# eeZeeSwitch.net
KiCad netlist of a schematic drawn in EAGLE
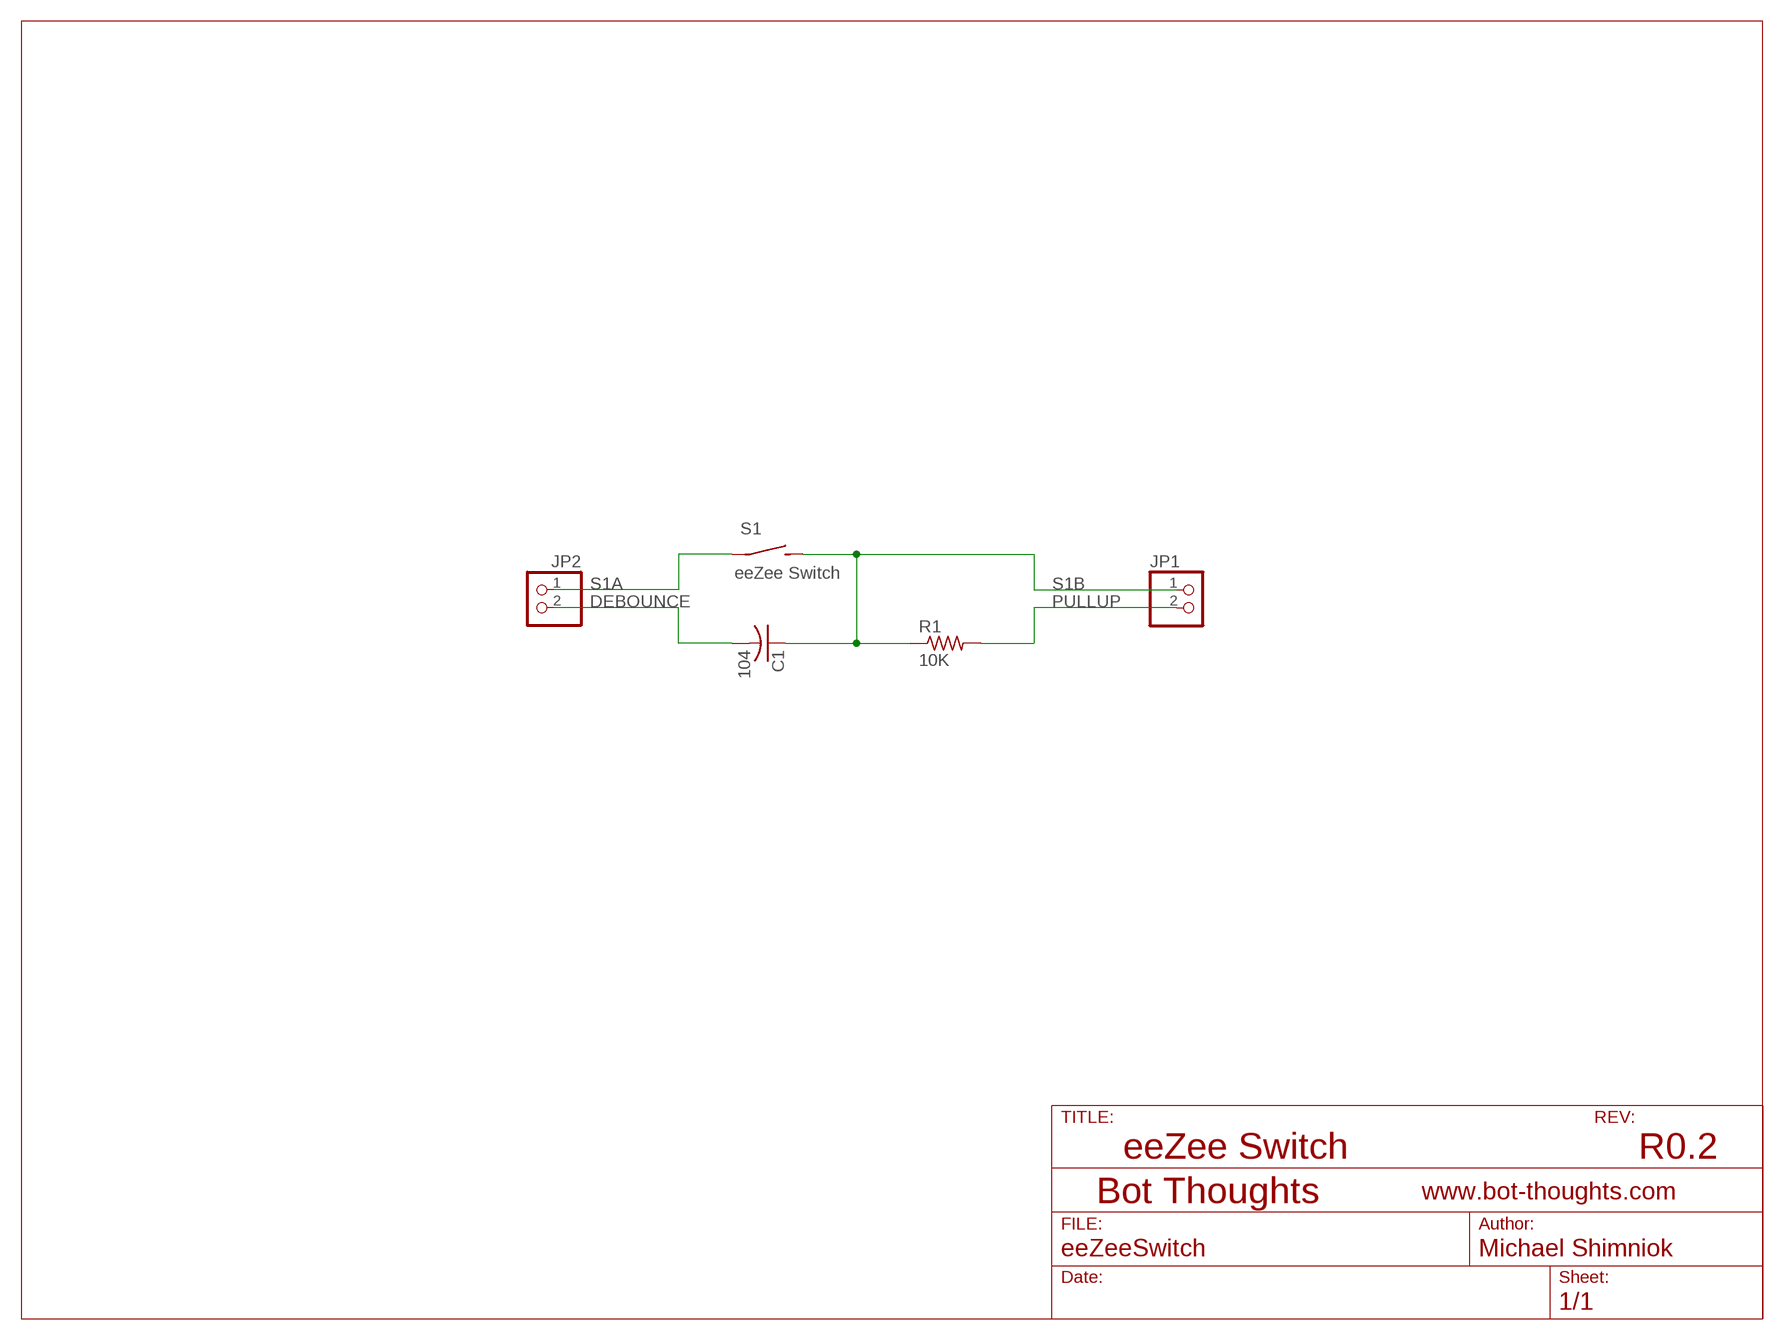
[diagram p0: schematic, sheet 1]

(export (version "E")
  (design (tool "Eeschema 10.0.6"))
  (components
    (comp (ref "C1")
      (value "104")
      (footprint "eagle-import:C0603")
      (libsource (lib "eagle-import") (part "C-USC0603"))
    )
    (comp (ref "JP1")
      (value "PINHD-1X02_2.54-S")
      (footprint "eagle-import:1X02-S")
      (libsource (lib "eagle-import") (part "PINHD-1X02_2.54-S"))
    )
    (comp (ref "JP2")
      (value "PINHD-1X02_2.54-S")
      (footprint "eagle-import:1X02-S")
      (libsource (lib "eagle-import") (part "PINHD-1X02_2.54-S"))
    )
    (comp (ref "R1")
      (value "10K")
      (footprint "eagle-import:R0603")
      (libsource (lib "eagle-import") (part "R-US_R0603"))
    )
    (comp (ref "S1")
      (value "eeZee Switch")
      (footprint "eagle-import:6MMTACTILE_RECT")
      (libsource (lib "eagle-import") (part "SPST_TAC_RECT1"))
    )
  )
  (nets
    (net (code "1") (name "/DEBOUNCE") (class "Default")
      (node (ref "C1") (pin "2") (pinfunction "2_2") (pintype "passive"))
      (node (ref "JP2") (pin "2") (pinfunction "2_2") (pintype "passive"))
    )
    (net (code "2") (name "/PULLUP") (class "Default")
      (node (ref "JP1") (pin "2") (pinfunction "2_2") (pintype "passive"))
      (node (ref "R1") (pin "2") (pinfunction "2_2") (pintype "passive"))
    )
    (net (code "3") (name "/S1A") (class "Default")
      (node (ref "JP2") (pin "1") (pinfunction "1_1") (pintype "passive"))
      (node (ref "S1") (pin "P$1") (pinfunction "P_P$1") (pintype "passive"))
    )
    (net (code "4") (name "/S1B") (class "Default")
      (node (ref "C1") (pin "1") (pinfunction "1_1") (pintype "passive"))
      (node (ref "JP1") (pin "1") (pinfunction "1_1") (pintype "passive"))
      (node (ref "R1") (pin "1") (pinfunction "1_1") (pintype "passive"))
      (node (ref "S1") (pin "P$2") (pinfunction "S_P$2") (pintype "passive"))
    )
  )
)
